# FontesLineares.net
KiCad netlist of a schematic drawn in Altium Designer
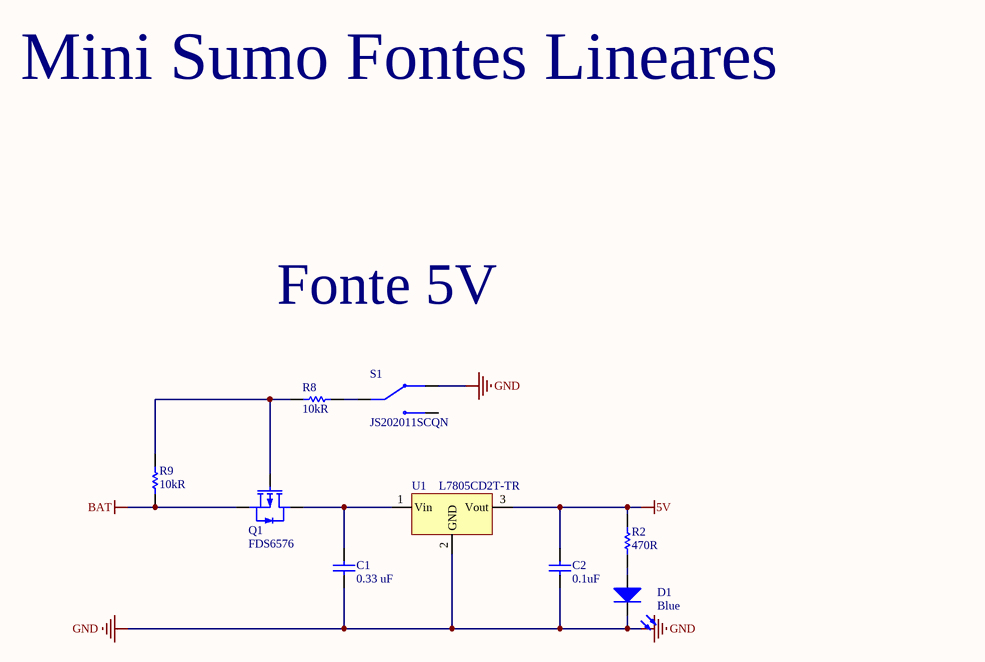
[diagram p0: FontesLineares.SchDoc]

(export (version "E")
  (design (tool "Eeschema 10.0.6"))
  (components
    (comp (ref "C1")
      (value "0.33 uF")
      (footprint "C0805")
      (description "CAP CER 0.33UF 25V X7R 0805")
      (fields
        (field (name "MANUFACTURER") "Murata Eletronics")
        (field (name "PART NUMBER") "GCM21BR71E334KA37K")
        (field (name "LIBRARY CONTROL - PERSON THAT CHECKED FOOTPRINT") "Nikaum")
        (field (name "LIBRARY CONTROL - PERSON THAT CHECKED SCHEMATIC") "Nikaum")
        (field (name "LIBRARY CONTROL - PERSON THAT DID THE LAST UPDATE FOOTPRINT") "Nikaum")
        (field (name "LIBRARY CONTROL - PERSON THAT DID THE LAST UPDATE SCHEMATIC") "Nikaum")
      )
      (libsource (lib "Uai!Tecas") (part "GCM21BR71E334KA37K"))
    )
    (comp (ref "C2")
      (value "0.1uF")
      (footprint "C0805")
      (description "CAP CER 0.1uF 25V X7R 0805")
      (fields
        (field (name "MANUFACTURER") "Kemet")
        (field (name "PART NUMBER") "C0805C104M3RACTU")
        (field (name "LIBRARY CONTROL - PERSON THAT CHECKED SCHEMATIC") "Guilherme")
        (field (name "LIBRARY CONTROL - PERSON THAT DID THE LAST UPDATE SCHEMATIC") "Marcos")
      )
      (libsource (lib "Uai!Tecas") (part "C0805C104M3RACTU"))
    )
    (comp (ref "D1")
      (value "Blue")
      (footprint "DIODO_2-SMD-3215")
      (description "LED 75mW BLUE 45MCD 3215")
      (fields
        (field (name "MANUFACTURER") "Everlight Electronics")
        (field (name "PART NUMBER") "EAST3215BA5")
        (field (name "LIBRARY CONTROL - PERSON THAT CHECKED FOOTPRINT") "Lucas")
        (field (name "LIBRARY CONTROL - PERSON THAT CHECKED SCHEMATIC") "Lucas")
        (field (name "LIBRARY CONTROL - PERSON THAT DID THE LAST UPDATE FOOTPRINT") "Stéfany (Ster)")
        (field (name "LIBRARY CONTROL - PERSON THAT DID THE LAST UPDATE SCHEMATIC") "Stéfany (Ster)")
      )
      (libsource (lib "Diodo") (part "EAST3215BA5"))
    )
    (comp (ref "Q1")
      (value "FDS6576")
      (footprint "SOIC-8")
      (description "MOSFET P-CH 20V 11A SOIC-8")
      (fields (field (name "PART NUMBER") "SOIC-8") (field (name "MANUFACTURER") "onsemi / Fairchild"))
      (libsource (lib "Uai!Tecas") (part "FDS6576"))
    )
    (comp (ref "R2")
      (value "470R")
      (footprint "RESISTOR_0805")
      (description "RES SMD 470 OHM 5% 1/8W 0805")
      (fields
        (field (name "MANUFACTURER") "Panasonic")
        (field (name "PART NUMBER") "667-ERJ-6GEYJ471V")
        (field (name "LIBRARY CONTROL - PERSON THAT CHECKED SCHEMATIC") "Marcos")
        (field (name "LIBRARY CONTROL - PERSON THAT DID THE LAST UPDATE FOOTPRINT") "Dalarme")
        (field (name "LIBRARY CONTROL - PERSON THAT DID THE LAST UPDATE SCHEMATIC") "Marcos")
      )
      (libsource (lib "Uai!Tecas") (part "ERJ-6GEYJ471V"))
    )
    (comp (ref "R8")
      (value "10kR")
      (footprint "RESISTOR_0603")
      (description "RES SMD 10K OHM 5% 1/10W 0603")
      (fields
        (field (name "MANUFACTURER") "Yageo")
        (field (name "PART NUMBER") "RC0603JR-0710KL")
        (field (name "LIBRARY CONTROL - PERSON THAT CHECKED SCHEMATIC") "Marcos")
        (field (name "LIBRARY CONTROL - PERSON THAT DID THE LAST UPDATE FOOTPRINT") "Dalarme")
        (field (name "LIBRARY CONTROL - PERSON THAT DID THE LAST UPDATE SCHEMATIC") "Marcos")
      )
      (libsource (lib "Uai!Tecas") (part "RC0603JR-0710KL"))
    )
    (comp (ref "R9")
      (value "10kR")
      (footprint "RESISTOR_0603")
      (description "RES SMD 10K OHM 5% 1/10W 0603")
      (fields
        (field (name "MANUFACTURER") "Yageo")
        (field (name "PART NUMBER") "RC0603JR-0710KL")
        (field (name "LIBRARY CONTROL - PERSON THAT CHECKED SCHEMATIC") "Marcos")
        (field (name "LIBRARY CONTROL - PERSON THAT DID THE LAST UPDATE FOOTPRINT") "Dalarme")
        (field (name "LIBRARY CONTROL - PERSON THAT DID THE LAST UPDATE SCHEMATIC") "Marcos")
      )
      (libsource (lib "Uai!Tecas") (part "RC0603JR-0710KL"))
    )
    (comp (ref "S1")
      (value "JS202011SCQN")
      (footprint "DPDT")
      (description "DEEP SWITCH 4 POSITIONS")
      (fields
        (field (name "MANUFACTURER") "C&K")
        (field (name "MOUSER PART NUMBER") "611-JS202011SCQN")
        (field (name "LIBRARY CONTROL - PERSON THAT CHECKED FOOTPRINT") "Nikaum")
        (field (name "LIBRARY CONTROL - PERSON THAT CHECKED SCHEMATIC") "Nikaum")
        (field (name "LIBRARY CONTROL - PERSON THAT DID THE LAST UPDATE FOOTPRINT") "Nikaum")
        (field (name "LIBRARY CONTROL - PERSON THAT DID THE LAST UPDATE SCHEMATIC") "Nikaum")
      )
      (libsource (lib "Diversos") (part "JS202011SCQN"))
    )
    (comp (ref "U1")
      (value "L7805CD2T-TR")
      (footprint "D2PAK")
      (description "IC REG LINEAR 5V 1A D2PAK")
      (fields
        (field (name "MANUFACTURER") "ST")
        (field (name "LIBRARY CONTROL - PERSON THAT CHECKED FOOTPRINT") "Nícolas")
        (field (name "LIBRARY CONTROL - PERSON THAT CHECKED SCHEMATIC") "Nícolas")
        (field (name "LIBRARY CONTROL - PERSON THAT DID THE LAST UPDATE SCHEMATIC") "Nícolas")
      )
      (libsource (lib "Uai!Tecas") (part "L7805CD2T-TR"))
    )
  )
  (nets
    (net (code "1") (name "5V") (class "Default")
      (node (ref "C2") (pin "2") (pinfunction "2_2") (pintype "passive"))
      (node (ref "R2") (pin "2") (pinfunction "2_2") (pintype "passive"))
      (node (ref "U1") (pin "3") (pinfunction "Vout_3") (pintype "power_in"))
    )
    (net (code "2") (name "BAT") (class "Default")
      (node (ref "Q1") (pin "S") (pinfunction "S_S") (pintype "passive"))
      (node (ref "R9") (pin "1") (pinfunction "1_1") (pintype "passive"))
    )
    (net (code "3") (name "GND") (class "Default")
      (node (ref "C1") (pin "1") (pinfunction "1_1") (pintype "passive"))
      (node (ref "C2") (pin "1") (pinfunction "1_1") (pintype "passive"))
      (node (ref "D1") (pin "C") (pinfunction "C_C") (pintype "passive"))
      (node (ref "S1") (pin "A2") (pinfunction "4_A2") (pintype "passive"))
      (node (ref "U1") (pin "2") (pinfunction "GND_2") (pintype "power_in"))
    )
    (net (code "4") (name "Net-(D1-PadA)") (class "Default")
      (node (ref "D1") (pin "A") (pinfunction "A_A") (pintype "passive"))
      (node (ref "R2") (pin "1") (pinfunction "1_1") (pintype "passive"))
    )
    (net (code "5") (name "Net-(Q1-PadG)") (class "Default")
      (node (ref "Q1") (pin "G") (pinfunction "G_G") (pintype "passive"))
      (node (ref "R8") (pin "2") (pinfunction "2_2") (pintype "passive"))
      (node (ref "R9") (pin "2") (pinfunction "2_2") (pintype "passive"))
    )
    (net (code "6") (name "Net-(S1-1)") (class "Default")
      (node (ref "R8") (pin "1") (pinfunction "1_1") (pintype "passive"))
      (node (ref "S1") (pin "A1") (pinfunction "1_A1") (pintype "passive"))
    )
    (net (code "7") (name "Net-(U1-Vin)") (class "Default")
      (node (ref "C1") (pin "2") (pinfunction "2_2") (pintype "passive"))
      (node (ref "Q1") (pin "D") (pinfunction "D_D") (pintype "passive"))
      (node (ref "U1") (pin "1") (pinfunction "Vin_1") (pintype "power_in"))
    )
    (net (code "8") (name "unconnected-(S1-3-PadA3)") (class "Default")
      (node (ref "S1") (pin "A3") (pinfunction "3_A3") (pintype "passive"))
    )
  )
)
